# ArduinoUhr_VFD.net
KiCad netlist of a schematic drawn in EAGLE
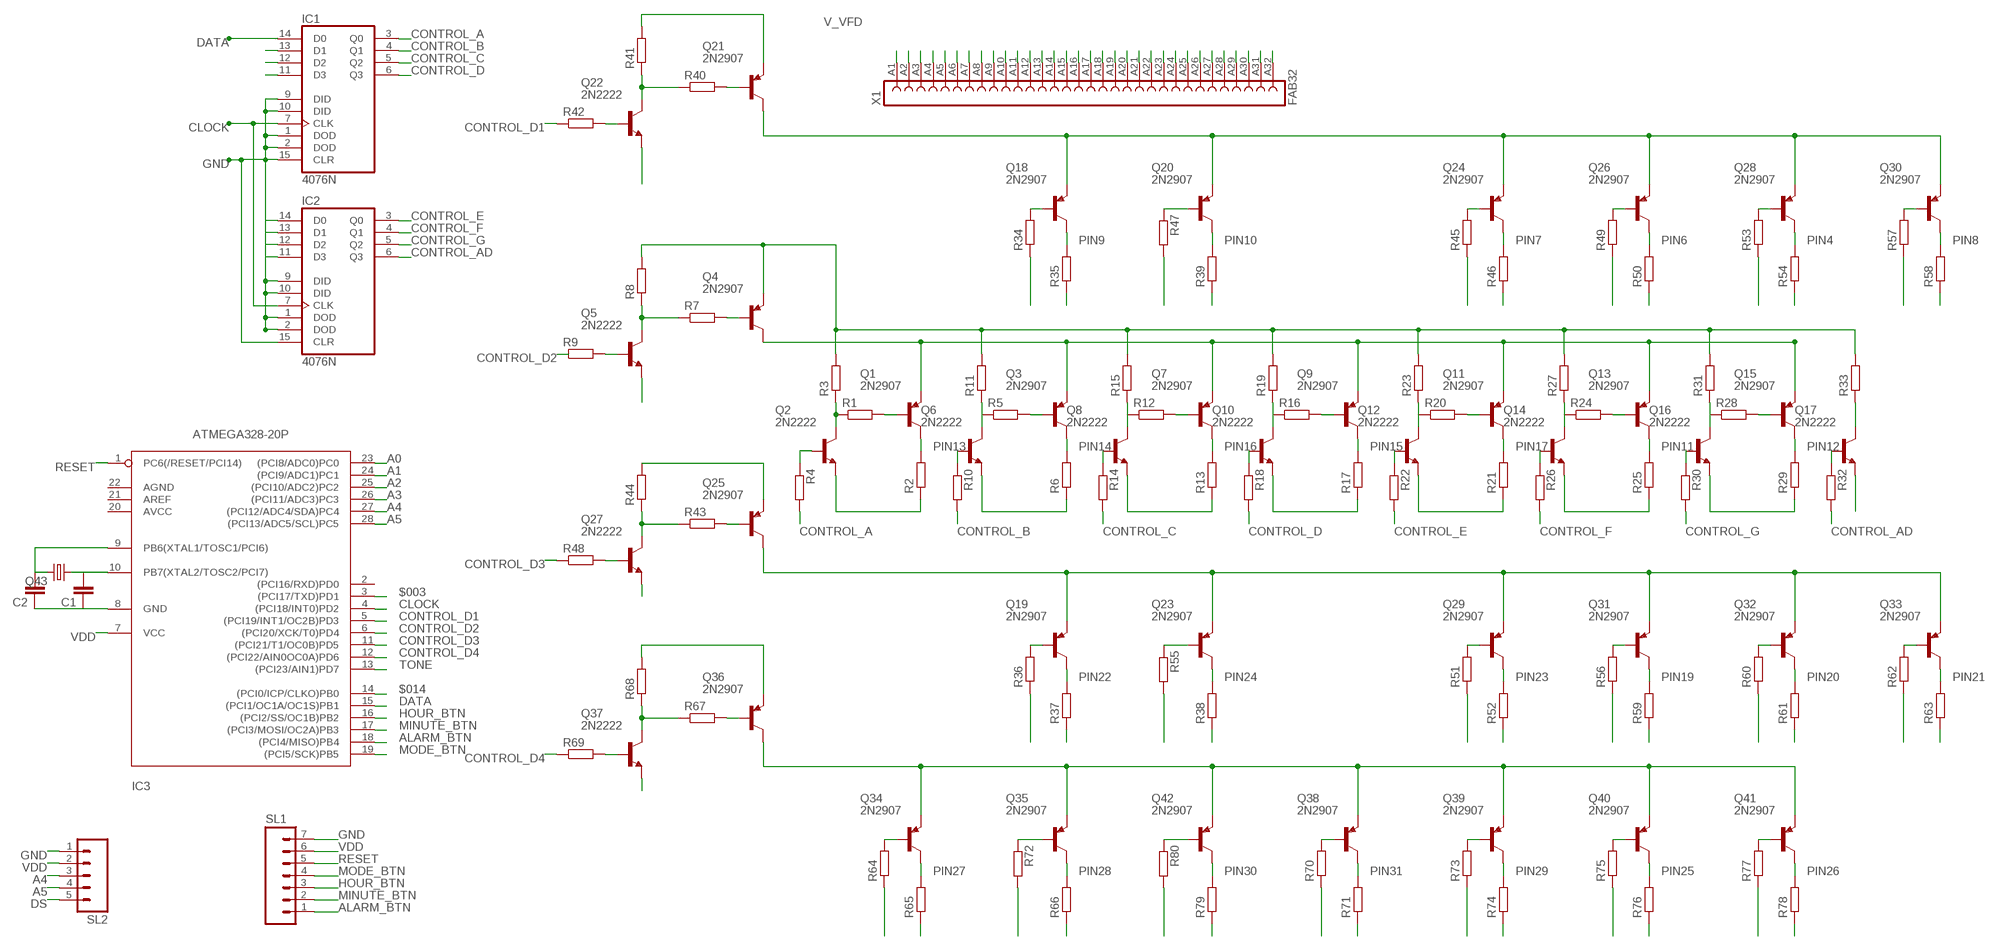
[diagram p0: schematic, sheet 1]

(export (version "E")
  (design (tool "Eeschema 10.0.6"))
  (components
    (comp (ref "C1")
      (value "C-EU025-024X044")
      (footprint "eagle-import:C025-024X044")
      (libsource (lib "eagle-import") (part "C-EU025-024X044"))
    )
    (comp (ref "C2")
      (value "C-EU025-024X044")
      (footprint "eagle-import:C025-024X044")
      (libsource (lib "eagle-import") (part "C-EU025-024X044"))
    )
    (comp (ref "IC1")
      (value "4076N")
      (footprint "eagle-import:DIL16")
      (libsource (lib "eagle-import") (part "4076N"))
    )
    (comp (ref "IC2")
      (value "4076N")
      (footprint "eagle-import:DIL16")
      (libsource (lib "eagle-import") (part "4076N"))
    )
    (comp (ref "IC3")
      (value "ATMEGA328-20P")
      (footprint "eagle-import:DIL28-3")
      (libsource (lib "eagle-import") (part "ATMEGA328P-20"))
    )
    (comp (ref "Q1")
      (value "2N2907")
      (footprint "eagle-import:TO18")
      (libsource (lib "eagle-import") (part "2N2907"))
    )
    (comp (ref "Q2")
      (value "2N2222")
      (footprint "eagle-import:TO18")
      (libsource (lib "eagle-import") (part "2N2222"))
    )
    (comp (ref "Q3")
      (value "2N2907")
      (footprint "eagle-import:TO18")
      (libsource (lib "eagle-import") (part "2N2907"))
    )
    (comp (ref "Q4")
      (value "2N2907")
      (footprint "eagle-import:TO18")
      (libsource (lib "eagle-import") (part "2N2907"))
    )
    (comp (ref "Q5")
      (value "2N2222")
      (footprint "eagle-import:TO18")
      (libsource (lib "eagle-import") (part "2N2222"))
    )
    (comp (ref "Q6")
      (value "2N2222")
      (footprint "eagle-import:TO18")
      (libsource (lib "eagle-import") (part "2N2222"))
    )
    (comp (ref "Q7")
      (value "2N2907")
      (footprint "eagle-import:TO18")
      (libsource (lib "eagle-import") (part "2N2907"))
    )
    (comp (ref "Q8")
      (value "2N2222")
      (footprint "eagle-import:TO18")
      (libsource (lib "eagle-import") (part "2N2222"))
    )
    (comp (ref "Q9")
      (value "2N2907")
      (footprint "eagle-import:TO18")
      (libsource (lib "eagle-import") (part "2N2907"))
    )
    (comp (ref "Q10")
      (value "2N2222")
      (footprint "eagle-import:TO18")
      (libsource (lib "eagle-import") (part "2N2222"))
    )
    (comp (ref "Q11")
      (value "2N2907")
      (footprint "eagle-import:TO18")
      (libsource (lib "eagle-import") (part "2N2907"))
    )
    (comp (ref "Q12")
      (value "2N2222")
      (footprint "eagle-import:TO18")
      (libsource (lib "eagle-import") (part "2N2222"))
    )
    (comp (ref "Q13")
      (value "2N2907")
      (footprint "eagle-import:TO18")
      (libsource (lib "eagle-import") (part "2N2907"))
    )
    (comp (ref "Q14")
      (value "2N2222")
      (footprint "eagle-import:TO18")
      (libsource (lib "eagle-import") (part "2N2222"))
    )
    (comp (ref "Q15")
      (value "2N2907")
      (footprint "eagle-import:TO18")
      (libsource (lib "eagle-import") (part "2N2907"))
    )
    (comp (ref "Q16")
      (value "2N2222")
      (footprint "eagle-import:TO18")
      (libsource (lib "eagle-import") (part "2N2222"))
    )
    (comp (ref "Q17")
      (value "2N2222")
      (footprint "eagle-import:TO18")
      (libsource (lib "eagle-import") (part "2N2222"))
    )
    (comp (ref "Q18")
      (value "2N2907")
      (footprint "eagle-import:TO18")
      (libsource (lib "eagle-import") (part "2N2907"))
    )
    (comp (ref "Q19")
      (value "2N2907")
      (footprint "eagle-import:TO18")
      (libsource (lib "eagle-import") (part "2N2907"))
    )
    (comp (ref "Q20")
      (value "2N2907")
      (footprint "eagle-import:TO18")
      (libsource (lib "eagle-import") (part "2N2907"))
    )
    (comp (ref "Q21")
      (value "2N2907")
      (footprint "eagle-import:TO18")
      (libsource (lib "eagle-import") (part "2N2907"))
    )
    (comp (ref "Q22")
      (value "2N2222")
      (footprint "eagle-import:TO18")
      (libsource (lib "eagle-import") (part "2N2222"))
    )
    (comp (ref "Q23")
      (value "2N2907")
      (footprint "eagle-import:TO18")
      (libsource (lib "eagle-import") (part "2N2907"))
    )
    (comp (ref "Q24")
      (value "2N2907")
      (footprint "eagle-import:TO18")
      (libsource (lib "eagle-import") (part "2N2907"))
    )
    (comp (ref "Q25")
      (value "2N2907")
      (footprint "eagle-import:TO18")
      (libsource (lib "eagle-import") (part "2N2907"))
    )
    (comp (ref "Q26")
      (value "2N2907")
      (footprint "eagle-import:TO18")
      (libsource (lib "eagle-import") (part "2N2907"))
    )
    (comp (ref "Q27")
      (value "2N2222")
      (footprint "eagle-import:TO18")
      (libsource (lib "eagle-import") (part "2N2222"))
    )
    (comp (ref "Q28")
      (value "2N2907")
      (footprint "eagle-import:TO18")
      (libsource (lib "eagle-import") (part "2N2907"))
    )
    (comp (ref "Q29")
      (value "2N2907")
      (footprint "eagle-import:TO18")
      (libsource (lib "eagle-import") (part "2N2907"))
    )
    (comp (ref "Q30")
      (value "2N2907")
      (footprint "eagle-import:TO18")
      (libsource (lib "eagle-import") (part "2N2907"))
    )
    (comp (ref "Q31")
      (value "2N2907")
      (footprint "eagle-import:TO18")
      (libsource (lib "eagle-import") (part "2N2907"))
    )
    (comp (ref "Q32")
      (value "2N2907")
      (footprint "eagle-import:TO18")
      (libsource (lib "eagle-import") (part "2N2907"))
    )
    (comp (ref "Q33")
      (value "2N2907")
      (footprint "eagle-import:TO18")
      (libsource (lib "eagle-import") (part "2N2907"))
    )
    (comp (ref "Q34")
      (value "2N2907")
      (footprint "eagle-import:TO18")
      (libsource (lib "eagle-import") (part "2N2907"))
    )
    (comp (ref "Q35")
      (value "2N2907")
      (footprint "eagle-import:TO18")
      (libsource (lib "eagle-import") (part "2N2907"))
    )
    (comp (ref "Q36")
      (value "2N2907")
      (footprint "eagle-import:TO18")
      (libsource (lib "eagle-import") (part "2N2907"))
    )
    (comp (ref "Q37")
      (value "2N2222")
      (footprint "eagle-import:TO18")
      (libsource (lib "eagle-import") (part "2N2222"))
    )
    (comp (ref "Q38")
      (value "2N2907")
      (footprint "eagle-import:TO18")
      (libsource (lib "eagle-import") (part "2N2907"))
    )
    (comp (ref "Q39")
      (value "2N2907")
      (footprint "eagle-import:TO18")
      (libsource (lib "eagle-import") (part "2N2907"))
    )
    (comp (ref "Q40")
      (value "2N2907")
      (footprint "eagle-import:TO18")
      (libsource (lib "eagle-import") (part "2N2907"))
    )
    (comp (ref "Q41")
      (value "2N2907")
      (footprint "eagle-import:TO18")
      (libsource (lib "eagle-import") (part "2N2907"))
    )
    (comp (ref "Q42")
      (value "2N2907")
      (footprint "eagle-import:TO18")
      (libsource (lib "eagle-import") (part "2N2907"))
    )
    (comp (ref "Q43")
      (value "CRYSTALHC49S")
      (footprint "eagle-import:HC49_S")
      (libsource (lib "eagle-import") (part "CRYSTALHC49S"))
    )
    (comp (ref "R1")
      (value "R-EU_0411/3V")
      (footprint "eagle-import:0411V")
      (libsource (lib "eagle-import") (part "rcl_334_R-EU_0411/3V"))
    )
    (comp (ref "R2")
      (value "R-EU_0204/7")
      (footprint "eagle-import:0204_7")
      (libsource (lib "eagle-import") (part "R-EU_0204/7"))
    )
    (comp (ref "R3")
      (value "R-EU_0204/7")
      (footprint "eagle-import:0204_7")
      (libsource (lib "eagle-import") (part "R-EU_0204/7"))
    )
    (comp (ref "R4")
      (value "R-EU_0204/7")
      (footprint "eagle-import:0204_7")
      (libsource (lib "eagle-import") (part "R-EU_0204/7"))
    )
    (comp (ref "R5")
      (value "R-EU_0204/7")
      (footprint "eagle-import:0204_7")
      (libsource (lib "eagle-import") (part "R-EU_0204/7"))
    )
    (comp (ref "R6")
      (value "R-EU_0204/7")
      (footprint "eagle-import:0204_7")
      (libsource (lib "eagle-import") (part "R-EU_0204/7"))
    )
    (comp (ref "R7")
      (value "R-EU_0204/2V")
      (footprint "eagle-import:0204V")
      (libsource (lib "eagle-import") (part "rcl_334_R-EU_0204/2V"))
    )
    (comp (ref "R8")
      (value "R-EU_0204/2V")
      (footprint "eagle-import:0204V")
      (libsource (lib "eagle-import") (part "rcl_334_R-EU_0204/2V"))
    )
    (comp (ref "R9")
      (value "R-EU_0204/7")
      (footprint "eagle-import:0204_7")
      (libsource (lib "eagle-import") (part "R-EU_0204/7"))
    )
    (comp (ref "R10")
      (value "R-EU_0204/7")
      (footprint "eagle-import:0204_7")
      (libsource (lib "eagle-import") (part "R-EU_0204/7"))
    )
    (comp (ref "R11")
      (value "R-EU_0204/7")
      (footprint "eagle-import:0204_7")
      (libsource (lib "eagle-import") (part "R-EU_0204/7"))
    )
    (comp (ref "R12")
      (value "R-EU_0411/3V")
      (footprint "eagle-import:0411V")
      (libsource (lib "eagle-import") (part "rcl_334_R-EU_0411/3V"))
    )
    (comp (ref "R13")
      (value "R-EU_0204/7")
      (footprint "eagle-import:0204_7")
      (libsource (lib "eagle-import") (part "R-EU_0204/7"))
    )
    (comp (ref "R14")
      (value "R-EU_0204/7")
      (footprint "eagle-import:0204_7")
      (libsource (lib "eagle-import") (part "R-EU_0204/7"))
    )
    (comp (ref "R15")
      (value "R-EU_0204/7")
      (footprint "eagle-import:0204_7")
      (libsource (lib "eagle-import") (part "R-EU_0204/7"))
    )
    (comp (ref "R16")
      (value "R-EU_0204/7")
      (footprint "eagle-import:0204_7")
      (libsource (lib "eagle-import") (part "R-EU_0204/7"))
    )
    (comp (ref "R17")
      (value "R-EU_0204/7")
      (footprint "eagle-import:0204_7")
      (libsource (lib "eagle-import") (part "R-EU_0204/7"))
    )
    (comp (ref "R18")
      (value "R-EU_0204/7")
      (footprint "eagle-import:0204_7")
      (libsource (lib "eagle-import") (part "R-EU_0204/7"))
    )
    (comp (ref "R19")
      (value "R-EU_0204/7")
      (footprint "eagle-import:0204_7")
      (libsource (lib "eagle-import") (part "R-EU_0204/7"))
    )
    (comp (ref "R20")
      (value "R-EU_0411/3V")
      (footprint "eagle-import:0411V")
      (libsource (lib "eagle-import") (part "rcl_334_R-EU_0411/3V"))
    )
    (comp (ref "R21")
      (value "R-EU_0204/7")
      (footprint "eagle-import:0204_7")
      (libsource (lib "eagle-import") (part "R-EU_0204/7"))
    )
    (comp (ref "R22")
      (value "R-EU_0204/7")
      (footprint "eagle-import:0204_7")
      (libsource (lib "eagle-import") (part "R-EU_0204/7"))
    )
    (comp (ref "R23")
      (value "R-EU_0204/7")
      (footprint "eagle-import:0204_7")
      (libsource (lib "eagle-import") (part "R-EU_0204/7"))
    )
    (comp (ref "R24")
      (value "R-EU_0204/7")
      (footprint "eagle-import:0204_7")
      (libsource (lib "eagle-import") (part "R-EU_0204/7"))
    )
    (comp (ref "R25")
      (value "R-EU_0204/7")
      (footprint "eagle-import:0204_7")
      (libsource (lib "eagle-import") (part "R-EU_0204/7"))
    )
    (comp (ref "R26")
      (value "R-EU_0204/7")
      (footprint "eagle-import:0204_7")
      (libsource (lib "eagle-import") (part "R-EU_0204/7"))
    )
    (comp (ref "R27")
      (value "R-EU_0204/7")
      (footprint "eagle-import:0204_7")
      (libsource (lib "eagle-import") (part "R-EU_0204/7"))
    )
    (comp (ref "R28")
      (value "R-EU_0411/3V")
      (footprint "eagle-import:0411V")
      (libsource (lib "eagle-import") (part "rcl_334_R-EU_0411/3V"))
    )
    (comp (ref "R29")
      (value "R-EU_0204/7")
      (footprint "eagle-import:0204_7")
      (libsource (lib "eagle-import") (part "R-EU_0204/7"))
    )
    (comp (ref "R30")
      (value "R-EU_0204/7")
      (footprint "eagle-import:0204_7")
      (libsource (lib "eagle-import") (part "R-EU_0204/7"))
    )
    (comp (ref "R31")
      (value "R-EU_0204/7")
      (footprint "eagle-import:0204_7")
      (libsource (lib "eagle-import") (part "R-EU_0204/7"))
    )
    (comp (ref "R32")
      (value "R-EU_0204/7")
      (footprint "eagle-import:0204_7")
      (libsource (lib "eagle-import") (part "R-EU_0204/7"))
    )
    (comp (ref "R33")
      (value "R-EU_0204/7")
      (footprint "eagle-import:0204_7")
      (libsource (lib "eagle-import") (part "R-EU_0204/7"))
    )
    (comp (ref "R34")
      (value "R-EU_0411/3V")
      (footprint "eagle-import:0411V")
      (libsource (lib "eagle-import") (part "rcl_334_R-EU_0411/3V"))
    )
    (comp (ref "R35")
      (value "R-EU_0204/7")
      (footprint "eagle-import:0204_7")
      (libsource (lib "eagle-import") (part "R-EU_0204/7"))
    )
    (comp (ref "R36")
      (value "R-EU_0204/7")
      (footprint "eagle-import:0204_7")
      (libsource (lib "eagle-import") (part "R-EU_0204/7"))
    )
    (comp (ref "R37")
      (value "R-EU_0204/7")
      (footprint "eagle-import:0204_7")
      (libsource (lib "eagle-import") (part "R-EU_0204/7"))
    )
    (comp (ref "R38")
      (value "R-EU_0204/7")
      (footprint "eagle-import:0204_7")
      (libsource (lib "eagle-import") (part "R-EU_0204/7"))
    )
    (comp (ref "R39")
      (value "R-EU_0204/7")
      (footprint "eagle-import:0204_7")
      (libsource (lib "eagle-import") (part "R-EU_0204/7"))
    )
    (comp (ref "R40")
      (value "R-EU_0204/2V")
      (footprint "eagle-import:0204V")
      (libsource (lib "eagle-import") (part "rcl_334_R-EU_0204/2V"))
    )
    (comp (ref "R41")
      (value "R-EU_0204/2V")
      (footprint "eagle-import:0204V")
      (libsource (lib "eagle-import") (part "rcl_334_R-EU_0204/2V"))
    )
    (comp (ref "R42")
      (value "R-EU_0204/7")
      (footprint "eagle-import:0204_7")
      (libsource (lib "eagle-import") (part "R-EU_0204/7"))
    )
    (comp (ref "R43")
      (value "R-EU_0204/2V")
      (footprint "eagle-import:0204V")
      (libsource (lib "eagle-import") (part "rcl_334_R-EU_0204/2V"))
    )
    (comp (ref "R44")
      (value "R-EU_0204/2V")
      (footprint "eagle-import:0204V")
      (libsource (lib "eagle-import") (part "rcl_334_R-EU_0204/2V"))
    )
    (comp (ref "R45")
      (value "R-EU_0204/7")
      (footprint "eagle-import:0204_7")
      (libsource (lib "eagle-import") (part "R-EU_0204/7"))
    )
    (comp (ref "R46")
      (value "R-EU_0204/7")
      (footprint "eagle-import:0204_7")
      (libsource (lib "eagle-import") (part "R-EU_0204/7"))
    )
    (comp (ref "R47")
      (value "R-EU_0204/7")
      (footprint "eagle-import:0204_7")
      (libsource (lib "eagle-import") (part "R-EU_0204/7"))
    )
    (comp (ref "R48")
      (value "R-EU_0204/7")
      (footprint "eagle-import:0204_7")
      (libsource (lib "eagle-import") (part "R-EU_0204/7"))
    )
    (comp (ref "R49")
      (value "R-EU_0204/7")
      (footprint "eagle-import:0204_7")
      (libsource (lib "eagle-import") (part "R-EU_0204/7"))
    )
    (comp (ref "R50")
      (value "R-EU_0204/7")
      (footprint "eagle-import:0204_7")
      (libsource (lib "eagle-import") (part "R-EU_0204/7"))
    )
    (comp (ref "R51")
      (value "R-EU_0204/7")
      (footprint "eagle-import:0204_7")
      (libsource (lib "eagle-import") (part "R-EU_0204/7"))
    )
    (comp (ref "R52")
      (value "R-EU_0204/7")
      (footprint "eagle-import:0204_7")
      (libsource (lib "eagle-import") (part "R-EU_0204/7"))
    )
    (comp (ref "R53")
      (value "R-EU_0411/3V")
      (footprint "eagle-import:0411V")
      (libsource (lib "eagle-import") (part "rcl_334_R-EU_0411/3V"))
    )
    (comp (ref "R54")
      (value "R-EU_0204/7")
      (footprint "eagle-import:0204_7")
      (libsource (lib "eagle-import") (part "R-EU_0204/7"))
    )
    (comp (ref "R55")
      (value "R-EU_0411/3V")
      (footprint "eagle-import:0411V")
      (libsource (lib "eagle-import") (part "rcl_334_R-EU_0411/3V"))
    )
    (comp (ref "R56")
      (value "R-EU_0204/7")
      (footprint "eagle-import:0204_7")
      (libsource (lib "eagle-import") (part "R-EU_0204/7"))
    )
    (comp (ref "R57")
      (value "R-EU_0411/3V")
      (footprint "eagle-import:0411V")
      (libsource (lib "eagle-import") (part "rcl_334_R-EU_0411/3V"))
    )
    (comp (ref "R58")
      (value "R-EU_0204/7")
      (footprint "eagle-import:0204_7")
      (libsource (lib "eagle-import") (part "R-EU_0204/7"))
    )
    (comp (ref "R59")
      (value "R-EU_0204/7")
      (footprint "eagle-import:0204_7")
      (libsource (lib "eagle-import") (part "R-EU_0204/7"))
    )
    (comp (ref "R60")
      (value "R-EU_0411/3V")
      (footprint "eagle-import:0411V")
      (libsource (lib "eagle-import") (part "rcl_334_R-EU_0411/3V"))
    )
    (comp (ref "R61")
      (value "R-EU_0204/7")
      (footprint "eagle-import:0204_7")
      (libsource (lib "eagle-import") (part "R-EU_0204/7"))
    )
    (comp (ref "R62")
      (value "R-EU_0411/3V")
      (footprint "eagle-import:0411V")
      (libsource (lib "eagle-import") (part "rcl_334_R-EU_0411/3V"))
    )
    (comp (ref "R63")
      (value "R-EU_0204/7")
      (footprint "eagle-import:0204_7")
      (libsource (lib "eagle-import") (part "R-EU_0204/7"))
    )
    (comp (ref "R64")
      (value "R-EU_0204/7")
      (footprint "eagle-import:0204_7")
      (libsource (lib "eagle-import") (part "R-EU_0204/7"))
    )
    (comp (ref "R65")
      (value "R-EU_0204/7")
      (footprint "eagle-import:0204_7")
      (libsource (lib "eagle-import") (part "R-EU_0204/7"))
    )
    (comp (ref "R66")
      (value "R-EU_0204/7")
      (footprint "eagle-import:0204_7")
      (libsource (lib "eagle-import") (part "R-EU_0204/7"))
    )
    (comp (ref "R67")
      (value "R-EU_0204/2V")
      (footprint "eagle-import:0204V")
      (libsource (lib "eagle-import") (part "rcl_334_R-EU_0204/2V"))
    )
    (comp (ref "R68")
      (value "R-EU_0204/2V")
      (footprint "eagle-import:0204V")
      (libsource (lib "eagle-import") (part "rcl_334_R-EU_0204/2V"))
    )
    (comp (ref "R69")
      (value "R-EU_0204/7")
      (footprint "eagle-import:0204_7")
      (libsource (lib "eagle-import") (part "R-EU_0204/7"))
    )
    (comp (ref "R70")
      (value "R-EU_0204/7")
      (footprint "eagle-import:0204_7")
      (libsource (lib "eagle-import") (part "R-EU_0204/7"))
    )
    (comp (ref "R71")
      (value "R-EU_0204/7")
      (footprint "eagle-import:0204_7")
      (libsource (lib "eagle-import") (part "R-EU_0204/7"))
    )
    (comp (ref "R72")
      (value "R-EU_0411/3V")
      (footprint "eagle-import:0411V")
      (libsource (lib "eagle-import") (part "rcl_334_R-EU_0411/3V"))
    )
    (comp (ref "R73")
      (value "R-EU_0411/3V")
      (footprint "eagle-import:0411V")
      (libsource (lib "eagle-import") (part "rcl_334_R-EU_0411/3V"))
    )
    (comp (ref "R74")
      (value "R-EU_0204/7")
      (footprint "eagle-import:0204_7")
      (libsource (lib "eagle-import") (part "R-EU_0204/7"))
    )
    (comp (ref "R75")
      (value "R-EU_0411/3V")
      (footprint "eagle-import:0411V")
      (libsource (lib "eagle-import") (part "rcl_334_R-EU_0411/3V"))
    )
    (comp (ref "R76")
      (value "R-EU_0204/7")
      (footprint "eagle-import:0204_7")
      (libsource (lib "eagle-import") (part "R-EU_0204/7"))
    )
    (comp (ref "R77")
      (value "R-EU_0204/7")
      (footprint "eagle-import:0204_7")
      (libsource (lib "eagle-import") (part "R-EU_0204/7"))
    )
    (comp (ref "R78")
      (value "R-EU_0204/7")
      (footprint "eagle-import:0204_7")
      (libsource (lib "eagle-import") (part "R-EU_0204/7"))
    )
    (comp (ref "R79")
      (value "R-EU_0204/7")
      (footprint "eagle-import:0204_7")
      (libsource (lib "eagle-import") (part "R-EU_0204/7"))
    )
    (comp (ref "R80")
      (value "R-EU_0204/7")
      (footprint "eagle-import:0204_7")
      (libsource (lib "eagle-import") (part "R-EU_0204/7"))
    )
    (comp (ref "SL1")
      (value "M07")
      (footprint "eagle-import:07P")
      (libsource (lib "eagle-import") (part "M07"))
    )
    (comp (ref "SL2")
      (value "M05")
      (footprint "eagle-import:05P")
      (libsource (lib "eagle-import") (part "M05"))
    )
    (comp (ref "X1")
      (value "FAB32")
      (footprint "eagle-import:FAB32")
      (libsource (lib "eagle-import") (part "FAB32"))
    )
  )
  (nets
    (net (code "1") (name "/$003") (class "Default")
      (node (ref "IC3") (pin "3") (pinfunction "(PCI17/TXD)PD1_3") (pintype "bidirectional"))
    )
    (net (code "2") (name "/$014") (class "Default")
      (node (ref "IC3") (pin "14") (pinfunction "(PCI0/ICP/CLKO)PB0_14") (pintype "bidirectional"))
    )
    (net (code "3") (name "/A0") (class "Default")
      (node (ref "IC3") (pin "23") (pinfunction "(PCI8/ADC0)PC0_23") (pintype "bidirectional"))
    )
    (net (code "4") (name "/A1") (class "Default")
      (node (ref "IC3") (pin "24") (pinfunction "(PCI9/ADC1)PC1_24") (pintype "bidirectional"))
    )
    (net (code "5") (name "/A2") (class "Default")
      (node (ref "IC3") (pin "25") (pinfunction "(PCI10/ADC2)PC2_25") (pintype "bidirectional"))
    )
    (net (code "6") (name "/A3") (class "Default")
      (node (ref "IC3") (pin "26") (pinfunction "(PCI11/ADC3)PC3_26") (pintype "bidirectional"))
    )
    (net (code "7") (name "/A4") (class "Default")
      (node (ref "IC3") (pin "27") (pinfunction "(PCI12/ADC4/SDA)PC4_27") (pintype "bidirectional"))
      (node (ref "SL2") (pin "3") (pinfunction "3_3") (pintype "passive"))
    )
    (net (code "8") (name "/A5") (class "Default")
      (node (ref "IC3") (pin "28") (pinfunction "(PCI13/ADC5/SCL)PC5_28") (pintype "bidirectional"))
      (node (ref "SL2") (pin "4") (pinfunction "4_4") (pintype "passive"))
    )
    (net (code "9") (name "/ALARM_BTN") (class "Default")
      (node (ref "IC3") (pin "18") (pinfunction "(PCI4/MISO)PB4_18") (pintype "bidirectional"))
      (node (ref "SL1") (pin "1") (pinfunction "1_1") (pintype "passive"))
    )
    (net (code "10") (name "/CI_A") (class "Default")
      (node (ref "Q2") (pin "3") (pinfunction "C_3") (pintype "passive"))
      (node (ref "R1") (pin "1") (pinfunction "1_1") (pintype "passive"))
      (node (ref "R3") (pin "1") (pinfunction "1_1") (pintype "passive"))
      (node (ref "R64") (pin "1") (pinfunction "1_1") (pintype "passive"))
    )
    (net (code "11") (name "/CI_AD") (class "Default")
      (node (ref "Q17") (pin "3") (pinfunction "C_3") (pintype "passive"))
      (node (ref "R33") (pin "1") (pinfunction "1_1") (pintype "passive"))
      (node (ref "R57") (pin "1") (pinfunction "1_1") (pintype "passive"))
      (node (ref "R62") (pin "1") (pinfunction "1_1") (pintype "passive"))
    )
    (net (code "12") (name "/CI_B") (class "Default")
      (node (ref "Q6") (pin "3") (pinfunction "C_3") (pintype "passive"))
      (node (ref "R11") (pin "1") (pinfunction "1_1") (pintype "passive"))
      (node (ref "R34") (pin "1") (pinfunction "1_1") (pintype "passive"))
      (node (ref "R36") (pin "1") (pinfunction "1_1") (pintype "passive"))
      (node (ref "R5") (pin "1") (pinfunction "1_1") (pintype "passive"))
      (node (ref "R72") (pin "2") (pinfunction "2_2") (pintype "passive"))
    )
    (net (code "13") (name "/CI_C") (class "Default")
      (node (ref "Q8") (pin "3") (pinfunction "C_3") (pintype "passive"))
      (node (ref "R12") (pin "1") (pinfunction "1_1") (pintype "passive"))
      (node (ref "R15") (pin "1") (pinfunction "1_1") (pintype "passive"))
      (node (ref "R47") (pin "2") (pinfunction "2_2") (pintype "passive"))
      (node (ref "R55") (pin "2") (pinfunction "2_2") (pintype "passive"))
      (node (ref "R80") (pin "2") (pinfunction "2_2") (pintype "passive"))
    )
    (net (code "14") (name "/CI_D") (class "Default")
      (node (ref "Q10") (pin "3") (pinfunction "C_3") (pintype "passive"))
      (node (ref "R16") (pin "1") (pinfunction "1_1") (pintype "passive"))
      (node (ref "R19") (pin "1") (pinfunction "1_1") (pintype "passive"))
      (node (ref "R70") (pin "1") (pinfunction "1_1") (pintype "passive"))
    )
    (net (code "15") (name "/CI_E") (class "Default")
      (node (ref "Q12") (pin "3") (pinfunction "C_3") (pintype "passive"))
      (node (ref "R20") (pin "1") (pinfunction "1_1") (pintype "passive"))
      (node (ref "R23") (pin "1") (pinfunction "1_1") (pintype "passive"))
      (node (ref "R45") (pin "1") (pinfunction "1_1") (pintype "passive"))
      (node (ref "R51") (pin "1") (pinfunction "1_1") (pintype "passive"))
      (node (ref "R73") (pin "1") (pinfunction "1_1") (pintype "passive"))
    )
    (net (code "16") (name "/CI_F") (class "Default")
      (node (ref "Q14") (pin "3") (pinfunction "C_3") (pintype "passive"))
      (node (ref "R24") (pin "1") (pinfunction "1_1") (pintype "passive"))
      (node (ref "R27") (pin "1") (pinfunction "1_1") (pintype "passive"))
      (node (ref "R49") (pin "1") (pinfunction "1_1") (pintype "passive"))
      (node (ref "R56") (pin "1") (pinfunction "1_1") (pintype "passive"))
      (node (ref "R75") (pin "1") (pinfunction "1_1") (pintype "passive"))
    )
    (net (code "17") (name "/CI_G") (class "Default")
      (node (ref "Q16") (pin "3") (pinfunction "C_3") (pintype "passive"))
      (node (ref "R28") (pin "1") (pinfunction "1_1") (pintype "passive"))
      (node (ref "R31") (pin "1") (pinfunction "1_1") (pintype "passive"))
      (node (ref "R53") (pin "1") (pinfunction "1_1") (pintype "passive"))
      (node (ref "R60") (pin "1") (pinfunction "1_1") (pintype "passive"))
      (node (ref "R77") (pin "1") (pinfunction "1_1") (pintype "passive"))
    )
    (net (code "18") (name "/CLOCK") (class "Default")
      (node (ref "IC1") (pin "7") (pinfunction "CLK_7") (pintype "input"))
      (node (ref "IC2") (pin "7") (pinfunction "CLK_7") (pintype "input"))
      (node (ref "IC3") (pin "4") (pinfunction "(PCI18/INT0)PD2_4") (pintype "bidirectional"))
    )
    (net (code "19") (name "/CONTROL_A") (class "Default")
      (node (ref "IC1") (pin "13") (pinfunction "D1_13") (pintype "input"))
      (node (ref "IC1") (pin "3") (pinfunction "Q0_3") (pintype "output"))
      (node (ref "R4") (pin "2") (pinfunction "2_2") (pintype "passive"))
    )
    (net (code "20") (name "/CONTROL_AD") (class "Default")
      (node (ref "IC2") (pin "6") (pinfunction "Q3_6") (pintype "output"))
      (node (ref "R32") (pin "2") (pinfunction "2_2") (pintype "passive"))
    )
    (net (code "21") (name "/CONTROL_B") (class "Default")
      (node (ref "IC1") (pin "12") (pinfunction "D2_12") (pintype "input"))
      (node (ref "IC1") (pin "4") (pinfunction "Q1_4") (pintype "output"))
      (node (ref "R10") (pin "2") (pinfunction "2_2") (pintype "passive"))
    )
    (net (code "22") (name "/CONTROL_C") (class "Default")
      (node (ref "IC1") (pin "11") (pinfunction "D3_11") (pintype "input"))
      (node (ref "IC1") (pin "5") (pinfunction "Q2_5") (pintype "output"))
      (node (ref "R14") (pin "2") (pinfunction "2_2") (pintype "passive"))
    )
    (net (code "23") (name "/CONTROL_D") (class "Default")
      (node (ref "IC1") (pin "6") (pinfunction "Q3_6") (pintype "output"))
      (node (ref "IC2") (pin "14") (pinfunction "D0_14") (pintype "input"))
      (node (ref "R18") (pin "2") (pinfunction "2_2") (pintype "passive"))
    )
    (net (code "24") (name "/CONTROL_D1") (class "Default")
      (node (ref "IC3") (pin "5") (pinfunction "(PCI19/INT1/OC2B)PD3_5") (pintype "bidirectional"))
      (node (ref "R42") (pin "1") (pinfunction "1_1") (pintype "passive"))
    )
    (net (code "25") (name "/CONTROL_D2") (class "Default")
      (node (ref "IC3") (pin "6") (pinfunction "(PCI20/XCK/T0)PD4_6") (pintype "bidirectional"))
      (node (ref "R9") (pin "1") (pinfunction "1_1") (pintype "passive"))
    )
    (net (code "26") (name "/CONTROL_D3") (class "Default")
      (node (ref "IC3") (pin "11") (pinfunction "(PCI21/T1/OC0B)PD5_11") (pintype "bidirectional"))
      (node (ref "R48") (pin "1") (pinfunction "1_1") (pintype "passive"))
    )
    (net (code "27") (name "/CONTROL_D4") (class "Default")
      (node (ref "IC3") (pin "12") (pinfunction "(PCI22/AIN0OC0A)PD6_12") (pintype "bidirectional"))
      (node (ref "R69") (pin "1") (pinfunction "1_1") (pintype "passive"))
    )
    (net (code "28") (name "/CONTROL_E") (class "Default")
      (node (ref "IC2") (pin "13") (pinfunction "D1_13") (pintype "input"))
      (node (ref "IC2") (pin "3") (pinfunction "Q0_3") (pintype "output"))
      (node (ref "R22") (pin "2") (pinfunction "2_2") (pintype "passive"))
    )
    (net (code "29") (name "/CONTROL_F") (class "Default")
      (node (ref "IC2") (pin "12") (pinfunction "D2_12") (pintype "input"))
      (node (ref "IC2") (pin "4") (pinfunction "Q1_4") (pintype "output"))
      (node (ref "R26") (pin "2") (pinfunction "2_2") (pintype "passive"))
    )
    (net (code "30") (name "/CONTROL_G") (class "Default")
      (node (ref "IC2") (pin "11") (pinfunction "D3_11") (pintype "input"))
      (node (ref "IC2") (pin "5") (pinfunction "Q2_5") (pintype "output"))
      (node (ref "R30") (pin "2") (pinfunction "2_2") (pintype "passive"))
    )
    (net (code "31") (name "/DATA") (class "Default")
      (node (ref "IC1") (pin "14") (pinfunction "D0_14") (pintype "input"))
      (node (ref "IC3") (pin "15") (pinfunction "(PCI1/OC1A/OC1S)PB1_15") (pintype "bidirectional"))
    )
    (net (code "32") (name "/DS") (class "Default")
      (node (ref "SL2") (pin "5") (pinfunction "5_5") (pintype "passive"))
    )
    (net (code "33") (name "/GND") (class "Default")
      (node (ref "C1") (pin "1") (pinfunction "1_1") (pintype "passive"))
      (node (ref "C2") (pin "1") (pinfunction "1_1") (pintype "passive"))
      (node (ref "IC1") (pin "1") (pinfunction "DOD_1") (pintype "input"))
      (node (ref "IC1") (pin "10") (pinfunction "DID_10") (pintype "input"))
      (node (ref "IC1") (pin "15") (pinfunction "CLR_15") (pintype "input"))
      (node (ref "IC1") (pin "2") (pinfunction "DOD_2") (pintype "input"))
      (node (ref "IC1") (pin "9") (pinfunction "DID_9") (pintype "input"))
      (node (ref "IC2") (pin "1") (pinfunction "DOD_1") (pintype "input"))
      (node (ref "IC2") (pin "10") (pinfunction "DID_10") (pintype "input"))
      (node (ref "IC2") (pin "15") (pinfunction "CLR_15") (pintype "input"))
      (node (ref "IC2") (pin "2") (pinfunction "DOD_2") (pintype "input"))
      (node (ref "IC2") (pin "9") (pinfunction "DID_9") (pintype "input"))
      (node (ref "IC3") (pin "8") (pinfunction "GND_8") (pintype "bidirectional"))
      (node (ref "Q10") (pin "1") (pinfunction "E_1") (pintype "passive"))
      (node (ref "Q12") (pin "1") (pinfunction "E_1") (pintype "passive"))
      (node (ref "Q14") (pin "1") (pinfunction "E_1") (pintype "passive"))
      (node (ref "Q16") (pin "1") (pinfunction "E_1") (pintype "passive"))
      (node (ref "Q17") (pin "1") (pinfunction "E_1") (pintype "passive"))
      (node (ref "Q2") (pin "1") (pinfunction "E_1") (pintype "passive"))
      (node (ref "Q22") (pin "1") (pinfunction "E_1") (pintype "passive"))
      (node (ref "Q27") (pin "1") (pinfunction "E_1") (pintype "passive"))
      (node (ref "Q37") (pin "1") (pinfunction "E_1") (pintype "passive"))
      (node (ref "Q5") (pin "1") (pinfunction "E_1") (pintype "passive"))
      (node (ref "Q6") (pin "1") (pinfunction "E_1") (pintype "passive"))
      (node (ref "Q8") (pin "1") (pinfunction "E_1") (pintype "passive"))
      (node (ref "R13") (pin "1") (pinfunction "1_1") (pintype "passive"))
      (node (ref "R17") (pin "1") (pinfunction "1_1") (pintype "passive"))
      (node (ref "R2") (pin "1") (pinfunction "1_1") (pintype "passive"))
      (node (ref "R21") (pin "1") (pinfunction "1_1") (pintype "passive"))
      (node (ref "R25") (pin "1") (pinfunction "1_1") (pintype "passive"))
      (node (ref "R29") (pin "1") (pinfunction "1_1") (pintype "passive"))
      (node (ref "R35") (pin "1") (pinfunction "1_1") (pintype "passive"))
      (node (ref "R37") (pin "1") (pinfunction "1_1") (pintype "passive"))
      (node (ref "R38") (pin "1") (pinfunction "1_1") (pintype "passive"))
      (node (ref "R39") (pin "1") (pinfunction "1_1") (pintype "passive"))
      (node (ref "R46") (pin "1") (pinfunction "1_1") (pintype "passive"))
      (node (ref "R50") (pin "1") (pinfunction "1_1") (pintype "passive"))
      (node (ref "R52") (pin "1") (pinfunction "1_1") (pintype "passive"))
      (node (ref "R54") (pin "1") (pinfunction "1_1") (pintype "passive"))
      (node (ref "R58") (pin "1") (pinfunction "1_1") (pintype "passive"))
      (node (ref "R59") (pin "1") (pinfunction "1_1") (pintype "passive"))
      (node (ref "R6") (pin "1") (pinfunction "1_1") (pintype "passive"))
      (node (ref "R61") (pin "1") (pinfunction "1_1") (pintype "passive"))
      (node (ref "R63") (pin "1") (pinfunction "1_1") (pintype "passive"))
      (node (ref "R65") (pin "1") (pinfunction "1_1") (pintype "passive"))
      (node (ref "R66") (pin "1") (pinfunction "1_1") (pintype "passive"))
      (node (ref "R71") (pin "1") (pinfunction "1_1") (pintype "passive"))
      (node (ref "R74") (pin "1") (pinfunction "1_1") (pintype "passive"))
      (node (ref "R76") (pin "1") (pinfunction "1_1") (pintype "passive"))
      (node (ref "R78") (pin "1") (pinfunction "1_1") (pintype "passive"))
      (node (ref "R79") (pin "1") (pinfunction "1_1") (pintype "passive"))
      (node (ref "SL1") (pin "7") (pinfunction "7_7") (pintype "passive"))
      (node (ref "SL2") (pin "1") (pinfunction "1_1") (pintype "passive"))
    )
    (net (code "34") (name "/HOUR_BTN") (class "Default")
      (node (ref "IC3") (pin "16") (pinfunction "(PCI2/SS/OC1B)PB2_16") (pintype "bidirectional"))
      (node (ref "SL1") (pin "3") (pinfunction "3_3") (pintype "passive"))
    )
    (net (code "35") (name "/MINUTE_BTN") (class "Default")
      (node (ref "IC3") (pin "17") (pinfunction "(PCI3/MOSI/OC2A)PB3_17") (pintype "bidirectional"))
      (node (ref "SL1") (pin "2") (pinfunction "2_2") (pintype "passive"))
    )
    (net (code "36") (name "/MODE_BTN") (class "Default")
      (node (ref "IC3") (pin "19") (pinfunction "(PCI5/SCK)PB5_19") (pintype "bidirectional"))
      (node (ref "SL1") (pin "4") (pinfunction "4_4") (pintype "passive"))
    )
    (net (code "37") (name "/PIN4") (class "Default")
      (node (ref "Q28") (pin "3") (pinfunction "C_3") (pintype "passive"))
      (node (ref "R54") (pin "2") (pinfunction "2_2") (pintype "passive"))
      (node (ref "X1") (pin "A4") (pinfunction "4_A4") (pintype "passive"))
    )
    (net (code "38") (name "/PIN6") (class "Default")
      (node (ref "Q26") (pin "3") (pinfunction "C_3") (pintype "passive"))
      (node (ref "R50") (pin "2") (pinfunction "2_2") (pintype "passive"))
      (node (ref "X1") (pin "A6") (pinfunction "6_A6") (pintype "passive"))
    )
    (net (code "39") (name "/PIN7") (class "Default")
      (node (ref "Q24") (pin "3") (pinfunction "C_3") (pintype "passive"))
      (node (ref "R46") (pin "2") (pinfunction "2_2") (pintype "passive"))
      (node (ref "X1") (pin "A7") (pinfunction "7_A7") (pintype "passive"))
    )
    (net (code "40") (name "/PIN8") (class "Default")
      (node (ref "Q30") (pin "3") (pinfunction "C_3") (pintype "passive"))
      (node (ref "R58") (pin "2") (pinfunction "2_2") (pintype "passive"))
      (node (ref "X1") (pin "A8") (pinfunction "8_A8") (pintype "passive"))
    )
    (net (code "41") (name "/PIN9") (class "Default")
      (node (ref "Q18") (pin "3") (pinfunction "C_3") (pintype "passive"))
      (node (ref "R35") (pin "2") (pinfunction "2_2") (pintype "passive"))
      (node (ref "X1") (pin "A9") (pinfunction "9_A9") (pintype "passive"))
    )
    (net (code "42") (name "/PIN10") (class "Default")
      (node (ref "Q20") (pin "3") (pinfunction "C_3") (pintype "passive"))
      (node (ref "R39") (pin "2") (pinfunction "2_2") (pintype "passive"))
      (node (ref "X1") (pin "A10") (pinfunction "10_A10") (pintype "passive"))
    )
    (net (code "43") (name "/PIN11") (class "Default")
      (node (ref "Q13") (pin "3") (pinfunction "C_3") (pintype "passive"))
      (node (ref "R25") (pin "2") (pinfunction "2_2") (pintype "passive"))
      (node (ref "X1") (pin "A11") (pinfunction "11_A11") (pintype "passive"))
    )
    (net (code "44") (name "/PIN12") (class "Default")
      (node (ref "Q15") (pin "3") (pinfunction "C_3") (pintype "passive"))
      (node (ref "R29") (pin "2") (pinfunction "2_2") (pintype "passive"))
      (node (ref "X1") (pin "A12") (pinfunction "12_A12") (pintype "passive"))
    )
    (net (code "45") (name "/PIN13") (class "Default")
      (node (ref "Q1") (pin "3") (pinfunction "C_3") (pintype "passive"))
      (node (ref "R2") (pin "2") (pinfunction "2_2") (pintype "passive"))
      (node (ref "X1") (pin "A13") (pinfunction "13_A13") (pintype "passive"))
    )
    (net (code "46") (name "/PIN14") (class "Default")
      (node (ref "Q3") (pin "3") (pinfunction "C_3") (pintype "passive"))
      (node (ref "R6") (pin "2") (pinfunction "2_2") (pintype "passive"))
      (node (ref "X1") (pin "A14") (pinfunction "14_A14") (pintype "passive"))
    )
    (net (code "47") (name "/PIN15") (class "Default")
      (node (ref "Q9") (pin "3") (pinfunction "C_3") (pintype "passive"))
      (node (ref "R17") (pin "2") (pinfunction "2_2") (pintype "passive"))
      (node (ref "X1") (pin "A15") (pinfunction "15_A15") (pintype "passive"))
    )
    (net (code "48") (name "/PIN16") (class "Default")
      (node (ref "Q7") (pin "3") (pinfunction "C_3") (pintype "passive"))
      (node (ref "R13") (pin "2") (pinfunction "2_2") (pintype "passive"))
      (node (ref "X1") (pin "A16") (pinfunction "16_A16") (pintype "passive"))
    )
    (net (code "49") (name "/PIN17") (class "Default")
      (node (ref "Q11") (pin "3") (pinfunction "C_3") (pintype "passive"))
      (node (ref "R21") (pin "2") (pinfunction "2_2") (pintype "passive"))
      (node (ref "X1") (pin "A17") (pinfunction "17_A17") (pintype "passive"))
    )
    (net (code "50") (name "/PIN19") (class "Default")
      (node (ref "Q31") (pin "3") (pinfunction "C_3") (pintype "passive"))
      (node (ref "R59") (pin "2") (pinfunction "2_2") (pintype "passive"))
      (node (ref "X1") (pin "A19") (pinfunction "19_A19") (pintype "passive"))
    )
    (net (code "51") (name "/PIN20") (class "Default")
      (node (ref "Q32") (pin "3") (pinfunction "C_3") (pintype "passive"))
      (node (ref "R61") (pin "2") (pinfunction "2_2") (pintype "passive"))
      (node (ref "X1") (pin "A20") (pinfunction "20_A20") (pintype "passive"))
    )
    (net (code "52") (name "/PIN21") (class "Default")
      (node (ref "Q33") (pin "3") (pinfunction "C_3") (pintype "passive"))
      (node (ref "R63") (pin "2") (pinfunction "2_2") (pintype "passive"))
      (node (ref "X1") (pin "A21") (pinfunction "21_A21") (pintype "passive"))
    )
    (net (code "53") (name "/PIN22") (class "Default")
      (node (ref "Q19") (pin "3") (pinfunction "C_3") (pintype "passive"))
      (node (ref "R37") (pin "2") (pinfunction "2_2") (pintype "passive"))
      (node (ref "X1") (pin "A22") (pinfunction "22_A22") (pintype "passive"))
    )
    (net (code "54") (name "/PIN23") (class "Default")
      (node (ref "Q29") (pin "3") (pinfunction "C_3") (pintype "passive"))
      (node (ref "R52") (pin "2") (pinfunction "2_2") (pintype "passive"))
      (node (ref "X1") (pin "A23") (pinfunction "23_A23") (pintype "passive"))
    )
    (net (code "55") (name "/PIN24") (class "Default")
      (node (ref "Q23") (pin "3") (pinfunction "C_3") (pintype "passive"))
      (node (ref "R38") (pin "2") (pinfunction "2_2") (pintype "passive"))
      (node (ref "X1") (pin "A24") (pinfunction "24_A24") (pintype "passive"))
    )
    (net (code "56") (name "/PIN25") (class "Default")
      (node (ref "Q40") (pin "3") (pinfunction "C_3") (pintype "passive"))
      (node (ref "R76") (pin "2") (pinfunction "2_2") (pintype "passive"))
      (node (ref "X1") (pin "A25") (pinfunction "25_A25") (pintype "passive"))
    )
    (net (code "57") (name "/PIN26") (class "Default")
      (node (ref "Q41") (pin "3") (pinfunction "C_3") (pintype "passive"))
      (node (ref "R78") (pin "2") (pinfunction "2_2") (pintype "passive"))
      (node (ref "X1") (pin "A26") (pinfunction "26_A26") (pintype "passive"))
    )
    (net (code "58") (name "/PIN27") (class "Default")
      (node (ref "Q34") (pin "3") (pinfunction "C_3") (pintype "passive"))
      (node (ref "R65") (pin "2") (pinfunction "2_2") (pintype "passive"))
      (node (ref "X1") (pin "A27") (pinfunction "27_A27") (pintype "passive"))
    )
    (net (code "59") (name "/PIN28") (class "Default")
      (node (ref "Q35") (pin "3") (pinfunction "C_3") (pintype "passive"))
      (node (ref "R66") (pin "2") (pinfunction "2_2") (pintype "passive"))
      (node (ref "X1") (pin "A28") (pinfunction "28_A28") (pintype "passive"))
    )
    (net (code "60") (name "/PIN29") (class "Default")
      (node (ref "Q39") (pin "3") (pinfunction "C_3") (pintype "passive"))
      (node (ref "R74") (pin "2") (pinfunction "2_2") (pintype "passive"))
      (node (ref "X1") (pin "A29") (pinfunction "29_A29") (pintype "passive"))
    )
    (net (code "61") (name "/PIN30") (class "Default")
      (node (ref "Q42") (pin "3") (pinfunction "C_3") (pintype "passive"))
      (node (ref "R79") (pin "2") (pinfunction "2_2") (pintype "passive"))
      (node (ref "X1") (pin "A30") (pinfunction "30_A30") (pintype "passive"))
    )
    (net (code "62") (name "/PIN31") (class "Default")
      (node (ref "Q38") (pin "3") (pinfunction "C_3") (pintype "passive"))
      (node (ref "R71") (pin "2") (pinfunction "2_2") (pintype "passive"))
      (node (ref "X1") (pin "A31") (pinfunction "31_A31") (pintype "passive"))
    )
    (net (code "63") (name "/RESET") (class "Default")
      (node (ref "IC3") (pin "1") (pinfunction "PC6(/RESET/PCI14)_1") (pintype "bidirectional"))
      (node (ref "SL1") (pin "5") (pinfunction "5_5") (pintype "passive"))
    )
    (net (code "64") (name "/TONE") (class "Default")
      (node (ref "IC3") (pin "13") (pinfunction "(PCI23/AIN1)PD7_13") (pintype "bidirectional"))
    )
    (net (code "65") (name "/VDD") (class "Default")
      (node (ref "IC3") (pin "7") (pinfunction "VCC_7") (pintype "bidirectional"))
      (node (ref "SL1") (pin "6") (pinfunction "6_6") (pintype "passive"))
      (node (ref "SL2") (pin "2") (pinfunction "2_2") (pintype "passive"))
    )
    (net (code "66") (name "/V_VFD") (class "Default")
      (node (ref "Q21") (pin "1") (pinfunction "E_1") (pintype "passive"))
      (node (ref "Q25") (pin "1") (pinfunction "E_1") (pintype "passive"))
      (node (ref "Q36") (pin "1") (pinfunction "E_1") (pintype "passive"))
      (node (ref "Q4") (pin "1") (pinfunction "E_1") (pintype "passive"))
      (node (ref "R11") (pin "2") (pinfunction "2_2") (pintype "passive"))
      (node (ref "R15") (pin "2") (pinfunction "2_2") (pintype "passive"))
      (node (ref "R19") (pin "2") (pinfunction "2_2") (pintype "passive"))
      (node (ref "R23") (pin "2") (pinfunction "2_2") (pintype "passive"))
      (node (ref "R27") (pin "2") (pinfunction "2_2") (pintype "passive"))
      (node (ref "R3") (pin "2") (pinfunction "2_2") (pintype "passive"))
      (node (ref "R31") (pin "2") (pinfunction "2_2") (pintype "passive"))
      (node (ref "R33") (pin "2") (pinfunction "2_2") (pintype "passive"))
      (node (ref "R41") (pin "2") (pinfunction "2_2") (pintype "passive"))
      (node (ref "R44") (pin "2") (pinfunction "2_2") (pintype "passive"))
      (node (ref "R68") (pin "2") (pinfunction "2_2") (pintype "passive"))
      (node (ref "R8") (pin "2") (pinfunction "2_2") (pintype "passive"))
    )
    (net (code "67") (name "Net-(IC3-PB6(XTAL1{slash}TOSC1{slash}PCI6))") (class "Default")
      (node (ref "C2") (pin "2") (pinfunction "2_2") (pintype "passive"))
      (node (ref "IC3") (pin "9") (pinfunction "PB6(XTAL1/TOSC1/PCI6)_9") (pintype "bidirectional"))
      (node (ref "Q43") (pin "2") (pinfunction "2_2") (pintype "passive"))
    )
    (net (code "68") (name "Net-(IC3-PB7(XTAL2{slash}TOSC2{slash}PCI7))") (class "Default")
      (node (ref "C1") (pin "2") (pinfunction "2_2") (pintype "passive"))
      (node (ref "IC3") (pin "10") (pinfunction "PB7(XTAL2/TOSC2/PCI7)_10") (pintype "bidirectional"))
      (node (ref "Q43") (pin "1") (pinfunction "1_1") (pintype "passive"))
    )
    (net (code "69") (name "Net-(Q1-B)") (class "Default")
      (node (ref "Q1") (pin "2") (pinfunction "B_2") (pintype "passive"))
      (node (ref "R1") (pin "2") (pinfunction "2_2") (pintype "passive"))
    )
    (net (code "70") (name "Net-(Q1-E)") (class "Default")
      (node (ref "Q1") (pin "1") (pinfunction "E_1") (pintype "passive"))
      (node (ref "Q11") (pin "1") (pinfunction "E_1") (pintype "passive"))
      (node (ref "Q13") (pin "1") (pinfunction "E_1") (pintype "passive"))
      (node (ref "Q15") (pin "1") (pinfunction "E_1") (pintype "passive"))
      (node (ref "Q3") (pin "1") (pinfunction "E_1") (pintype "passive"))
      (node (ref "Q4") (pin "3") (pinfunction "C_3") (pintype "passive"))
      (node (ref "Q7") (pin "1") (pinfunction "E_1") (pintype "passive"))
      (node (ref "Q9") (pin "1") (pinfunction "E_1") (pintype "passive"))
    )
    (net (code "71") (name "Net-(Q2-B)") (class "Default")
      (node (ref "Q2") (pin "2") (pinfunction "B_2") (pintype "passive"))
      (node (ref "R4") (pin "1") (pinfunction "1_1") (pintype "passive"))
    )
    (net (code "72") (name "Net-(Q3-B)") (class "Default")
      (node (ref "Q3") (pin "2") (pinfunction "B_2") (pintype "passive"))
      (node (ref "R5") (pin "2") (pinfunction "2_2") (pintype "passive"))
    )
    (net (code "73") (name "Net-(Q4-B)") (class "Default")
      (node (ref "Q4") (pin "2") (pinfunction "B_2") (pintype "passive"))
      (node (ref "R7") (pin "2") (pinfunction "2_2") (pintype "passive"))
    )
    (net (code "74") (name "Net-(Q5-B)") (class "Default")
      (node (ref "Q5") (pin "2") (pinfunction "B_2") (pintype "passive"))
      (node (ref "R9") (pin "2") (pinfunction "2_2") (pintype "passive"))
    )
    (net (code "75") (name "Net-(Q5-C)") (class "Default")
      (node (ref "Q5") (pin "3") (pinfunction "C_3") (pintype "passive"))
      (node (ref "R7") (pin "1") (pinfunction "1_1") (pintype "passive"))
      (node (ref "R8") (pin "1") (pinfunction "1_1") (pintype "passive"))
    )
    (net (code "76") (name "Net-(Q6-B)") (class "Default")
      (node (ref "Q6") (pin "2") (pinfunction "B_2") (pintype "passive"))
      (node (ref "R10") (pin "1") (pinfunction "1_1") (pintype "passive"))
    )
    (net (code "77") (name "Net-(Q7-B)") (class "Default")
      (node (ref "Q7") (pin "2") (pinfunction "B_2") (pintype "passive"))
      (node (ref "R12") (pin "2") (pinfunction "2_2") (pintype "passive"))
    )
    (net (code "78") (name "Net-(Q8-B)") (class "Default")
      (node (ref "Q8") (pin "2") (pinfunction "B_2") (pintype "passive"))
      (node (ref "R14") (pin "1") (pinfunction "1_1") (pintype "passive"))
    )
    (net (code "79") (name "Net-(Q9-B)") (class "Default")
      (node (ref "Q9") (pin "2") (pinfunction "B_2") (pintype "passive"))
      (node (ref "R16") (pin "2") (pinfunction "2_2") (pintype "passive"))
    )
    (net (code "80") (name "Net-(Q10-B)") (class "Default")
      (node (ref "Q10") (pin "2") (pinfunction "B_2") (pintype "passive"))
      (node (ref "R18") (pin "1") (pinfunction "1_1") (pintype "passive"))
    )
    (net (code "81") (name "Net-(Q11-B)") (class "Default")
      (node (ref "Q11") (pin "2") (pinfunction "B_2") (pintype "passive"))
      (node (ref "R20") (pin "2") (pinfunction "2_2") (pintype "passive"))
    )
    (net (code "82") (name "Net-(Q12-B)") (class "Default")
      (node (ref "Q12") (pin "2") (pinfunction "B_2") (pintype "passive"))
      (node (ref "R22") (pin "1") (pinfunction "1_1") (pintype "passive"))
    )
    (net (code "83") (name "Net-(Q13-B)") (class "Default")
      (node (ref "Q13") (pin "2") (pinfunction "B_2") (pintype "passive"))
      (node (ref "R24") (pin "2") (pinfunction "2_2") (pintype "passive"))
    )
    (net (code "84") (name "Net-(Q14-B)") (class "Default")
      (node (ref "Q14") (pin "2") (pinfunction "B_2") (pintype "passive"))
      (node (ref "R26") (pin "1") (pinfunction "1_1") (pintype "passive"))
    )
    (net (code "85") (name "Net-(Q15-B)") (class "Default")
      (node (ref "Q15") (pin "2") (pinfunction "B_2") (pintype "passive"))
      (node (ref "R28") (pin "2") (pinfunction "2_2") (pintype "passive"))
    )
    (net (code "86") (name "Net-(Q16-B)") (class "Default")
      (node (ref "Q16") (pin "2") (pinfunction "B_2") (pintype "passive"))
      (node (ref "R30") (pin "1") (pinfunction "1_1") (pintype "passive"))
    )
    (net (code "87") (name "Net-(Q17-B)") (class "Default")
      (node (ref "Q17") (pin "2") (pinfunction "B_2") (pintype "passive"))
      (node (ref "R32") (pin "1") (pinfunction "1_1") (pintype "passive"))
    )
    (net (code "88") (name "Net-(Q18-B)") (class "Default")
      (node (ref "Q18") (pin "2") (pinfunction "B_2") (pintype "passive"))
      (node (ref "R34") (pin "2") (pinfunction "2_2") (pintype "passive"))
    )
    (net (code "89") (name "Net-(Q18-E)") (class "Default")
      (node (ref "Q18") (pin "1") (pinfunction "E_1") (pintype "passive"))
      (node (ref "Q20") (pin "1") (pinfunction "E_1") (pintype "passive"))
      (node (ref "Q21") (pin "3") (pinfunction "C_3") (pintype "passive"))
      (node (ref "Q24") (pin "1") (pinfunction "E_1") (pintype "passive"))
      (node (ref "Q26") (pin "1") (pinfunction "E_1") (pintype "passive"))
      (node (ref "Q28") (pin "1") (pinfunction "E_1") (pintype "passive"))
      (node (ref "Q30") (pin "1") (pinfunction "E_1") (pintype "passive"))
    )
    (net (code "90") (name "Net-(Q19-B)") (class "Default")
      (node (ref "Q19") (pin "2") (pinfunction "B_2") (pintype "passive"))
      (node (ref "R36") (pin "2") (pinfunction "2_2") (pintype "passive"))
    )
    (net (code "91") (name "Net-(Q19-E)") (class "Default")
      (node (ref "Q19") (pin "1") (pinfunction "E_1") (pintype "passive"))
      (node (ref "Q23") (pin "1") (pinfunction "E_1") (pintype "passive"))
      (node (ref "Q25") (pin "3") (pinfunction "C_3") (pintype "passive"))
      (node (ref "Q29") (pin "1") (pinfunction "E_1") (pintype "passive"))
      (node (ref "Q31") (pin "1") (pinfunction "E_1") (pintype "passive"))
      (node (ref "Q32") (pin "1") (pinfunction "E_1") (pintype "passive"))
      (node (ref "Q33") (pin "1") (pinfunction "E_1") (pintype "passive"))
    )
    (net (code "92") (name "Net-(Q20-B)") (class "Default")
      (node (ref "Q20") (pin "2") (pinfunction "B_2") (pintype "passive"))
      (node (ref "R47") (pin "1") (pinfunction "1_1") (pintype "passive"))
    )
    (net (code "93") (name "Net-(Q21-B)") (class "Default")
      (node (ref "Q21") (pin "2") (pinfunction "B_2") (pintype "passive"))
      (node (ref "R40") (pin "2") (pinfunction "2_2") (pintype "passive"))
    )
    (net (code "94") (name "Net-(Q22-B)") (class "Default")
      (node (ref "Q22") (pin "2") (pinfunction "B_2") (pintype "passive"))
      (node (ref "R42") (pin "2") (pinfunction "2_2") (pintype "passive"))
    )
    (net (code "95") (name "Net-(Q22-C)") (class "Default")
      (node (ref "Q22") (pin "3") (pinfunction "C_3") (pintype "passive"))
      (node (ref "R40") (pin "1") (pinfunction "1_1") (pintype "passive"))
      (node (ref "R41") (pin "1") (pinfunction "1_1") (pintype "passive"))
    )
    (net (code "96") (name "Net-(Q23-B)") (class "Default")
      (node (ref "Q23") (pin "2") (pinfunction "B_2") (pintype "passive"))
      (node (ref "R55") (pin "1") (pinfunction "1_1") (pintype "passive"))
    )
    (net (code "97") (name "Net-(Q24-B)") (class "Default")
      (node (ref "Q24") (pin "2") (pinfunction "B_2") (pintype "passive"))
      (node (ref "R45") (pin "2") (pinfunction "2_2") (pintype "passive"))
    )
    (net (code "98") (name "Net-(Q25-B)") (class "Default")
      (node (ref "Q25") (pin "2") (pinfunction "B_2") (pintype "passive"))
      (node (ref "R43") (pin "2") (pinfunction "2_2") (pintype "passive"))
    )
    (net (code "99") (name "Net-(Q26-B)") (class "Default")
      (node (ref "Q26") (pin "2") (pinfunction "B_2") (pintype "passive"))
      (node (ref "R49") (pin "2") (pinfunction "2_2") (pintype "passive"))
    )
    (net (code "100") (name "Net-(Q27-B)") (class "Default")
      (node (ref "Q27") (pin "2") (pinfunction "B_2") (pintype "passive"))
      (node (ref "R48") (pin "2") (pinfunction "2_2") (pintype "passive"))
    )
    (net (code "101") (name "Net-(Q27-C)") (class "Default")
      (node (ref "Q27") (pin "3") (pinfunction "C_3") (pintype "passive"))
      (node (ref "R43") (pin "1") (pinfunction "1_1") (pintype "passive"))
      (node (ref "R44") (pin "1") (pinfunction "1_1") (pintype "passive"))
    )
    (net (code "102") (name "Net-(Q28-B)") (class "Default")
      (node (ref "Q28") (pin "2") (pinfunction "B_2") (pintype "passive"))
      (node (ref "R53") (pin "2") (pinfunction "2_2") (pintype "passive"))
    )
    (net (code "103") (name "Net-(Q29-B)") (class "Default")
      (node (ref "Q29") (pin "2") (pinfunction "B_2") (pintype "passive"))
      (node (ref "R51") (pin "2") (pinfunction "2_2") (pintype "passive"))
    )
    (net (code "104") (name "Net-(Q30-B)") (class "Default")
      (node (ref "Q30") (pin "2") (pinfunction "B_2") (pintype "passive"))
      (node (ref "R57") (pin "2") (pinfunction "2_2") (pintype "passive"))
    )
    (net (code "105") (name "Net-(Q31-B)") (class "Default")
      (node (ref "Q31") (pin "2") (pinfunction "B_2") (pintype "passive"))
      (node (ref "R56") (pin "2") (pinfunction "2_2") (pintype "passive"))
    )
    (net (code "106") (name "Net-(Q32-B)") (class "Default")
      (node (ref "Q32") (pin "2") (pinfunction "B_2") (pintype "passive"))
      (node (ref "R60") (pin "2") (pinfunction "2_2") (pintype "passive"))
    )
    (net (code "107") (name "Net-(Q33-B)") (class "Default")
      (node (ref "Q33") (pin "2") (pinfunction "B_2") (pintype "passive"))
      (node (ref "R62") (pin "2") (pinfunction "2_2") (pintype "passive"))
    )
    (net (code "108") (name "Net-(Q34-B)") (class "Default")
      (node (ref "Q34") (pin "2") (pinfunction "B_2") (pintype "passive"))
      (node (ref "R64") (pin "2") (pinfunction "2_2") (pintype "passive"))
    )
    (net (code "109") (name "Net-(Q34-E)") (class "Default")
      (node (ref "Q34") (pin "1") (pinfunction "E_1") (pintype "passive"))
      (node (ref "Q35") (pin "1") (pinfunction "E_1") (pintype "passive"))
      (node (ref "Q36") (pin "3") (pinfunction "C_3") (pintype "passive"))
      (node (ref "Q38") (pin "1") (pinfunction "E_1") (pintype "passive"))
      (node (ref "Q39") (pin "1") (pinfunction "E_1") (pintype "passive"))
      (node (ref "Q40") (pin "1") (pinfunction "E_1") (pintype "passive"))
      (node (ref "Q41") (pin "1") (pinfunction "E_1") (pintype "passive"))
      (node (ref "Q42") (pin "1") (pinfunction "E_1") (pintype "passive"))
    )
    (net (code "110") (name "Net-(Q35-B)") (class "Default")
      (node (ref "Q35") (pin "2") (pinfunction "B_2") (pintype "passive"))
      (node (ref "R72") (pin "1") (pinfunction "1_1") (pintype "passive"))
    )
    (net (code "111") (name "Net-(Q36-B)") (class "Default")
      (node (ref "Q36") (pin "2") (pinfunction "B_2") (pintype "passive"))
      (node (ref "R67") (pin "2") (pinfunction "2_2") (pintype "passive"))
    )
    (net (code "112") (name "Net-(Q37-B)") (class "Default")
      (node (ref "Q37") (pin "2") (pinfunction "B_2") (pintype "passive"))
      (node (ref "R69") (pin "2") (pinfunction "2_2") (pintype "passive"))
    )
    (net (code "113") (name "Net-(Q37-C)") (class "Default")
      (node (ref "Q37") (pin "3") (pinfunction "C_3") (pintype "passive"))
      (node (ref "R67") (pin "1") (pinfunction "1_1") (pintype "passive"))
      (node (ref "R68") (pin "1") (pinfunction "1_1") (pintype "passive"))
    )
    (net (code "114") (name "Net-(Q38-B)") (class "Default")
      (node (ref "Q38") (pin "2") (pinfunction "B_2") (pintype "passive"))
      (node (ref "R70") (pin "2") (pinfunction "2_2") (pintype "passive"))
    )
    (net (code "115") (name "Net-(Q39-B)") (class "Default")
      (node (ref "Q39") (pin "2") (pinfunction "B_2") (pintype "passive"))
      (node (ref "R73") (pin "2") (pinfunction "2_2") (pintype "passive"))
    )
    (net (code "116") (name "Net-(Q40-B)") (class "Default")
      (node (ref "Q40") (pin "2") (pinfunction "B_2") (pintype "passive"))
      (node (ref "R75") (pin "2") (pinfunction "2_2") (pintype "passive"))
    )
    (net (code "117") (name "Net-(Q41-B)") (class "Default")
      (node (ref "Q41") (pin "2") (pinfunction "B_2") (pintype "passive"))
      (node (ref "R77") (pin "2") (pinfunction "2_2") (pintype "passive"))
    )
    (net (code "118") (name "Net-(Q42-B)") (class "Default")
      (node (ref "Q42") (pin "2") (pinfunction "B_2") (pintype "passive"))
      (node (ref "R80") (pin "1") (pinfunction "1_1") (pintype "passive"))
    )
    (net (code "119") (name "unconnected-(IC3-(PCI16{slash}RXD)PD0-Pad2)") (class "Default")
      (node (ref "IC3") (pin "2") (pinfunction "(PCI16/RXD)PD0_2") (pintype "bidirectional"))
    )
    (net (code "120") (name "unconnected-(IC3-AGND-Pad22)") (class "Default")
      (node (ref "IC3") (pin "22") (pinfunction "AGND_22") (pintype "bidirectional"))
    )
    (net (code "121") (name "unconnected-(IC3-AREF-Pad21)") (class "Default")
      (node (ref "IC3") (pin "21") (pinfunction "AREF_21") (pintype "bidirectional"))
    )
    (net (code "122") (name "unconnected-(IC3-AVCC-Pad20)") (class "Default")
      (node (ref "IC3") (pin "20") (pinfunction "AVCC_20") (pintype "bidirectional"))
    )
    (net (code "123") (name "unconnected-(X1-1-PadA1)") (class "Default")
      (node (ref "X1") (pin "A1") (pinfunction "1_A1") (pintype "passive"))
    )
    (net (code "124") (name "unconnected-(X1-2-PadA2)") (class "Default")
      (node (ref "X1") (pin "A2") (pinfunction "2_A2") (pintype "passive"))
    )
    (net (code "125") (name "unconnected-(X1-3-PadA3)") (class "Default")
      (node (ref "X1") (pin "A3") (pinfunction "3_A3") (pintype "passive"))
    )
    (net (code "126") (name "unconnected-(X1-5-PadA5)") (class "Default")
      (node (ref "X1") (pin "A5") (pinfunction "5_A5") (pintype "passive"))
    )
    (net (code "127") (name "unconnected-(X1-18-PadA18)") (class "Default")
      (node (ref "X1") (pin "A18") (pinfunction "18_A18") (pintype "passive"))
    )
    (net (code "128") (name "unconnected-(X1-32-PadA32)") (class "Default")
      (node (ref "X1") (pin "A32") (pinfunction "32_A32") (pintype "passive"))
    )
  )
)
